# tamiya_camrobo_face_dotstar.net
KiCad netlist of a schematic drawn in EAGLE
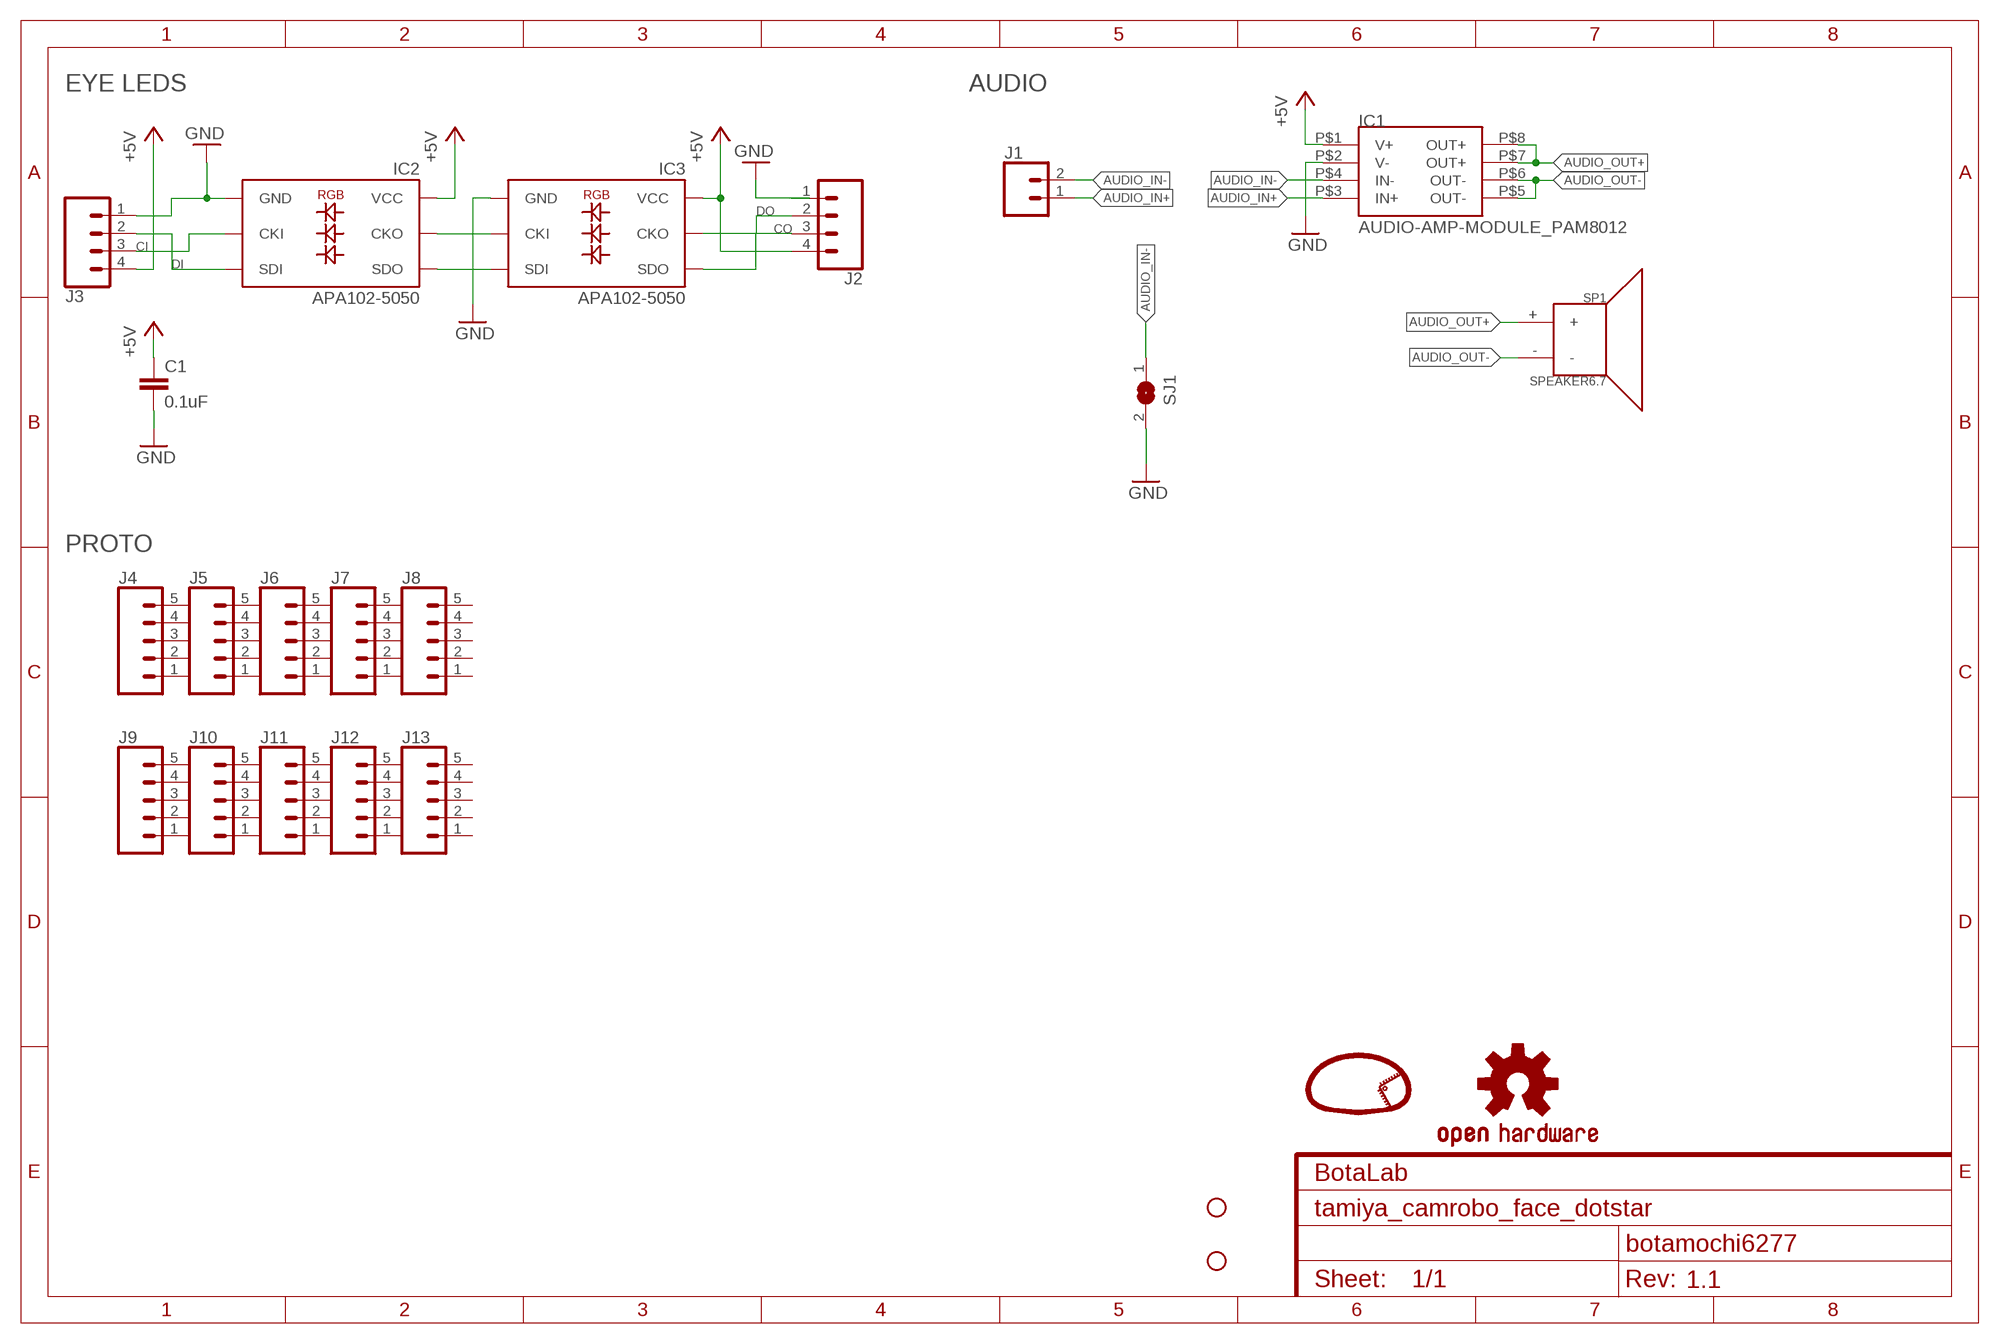
[diagram p0: schematic, sheet 1]

(export (version "E")
  (design (tool "Eeschema 10.0.6"))
  (components
    (comp (ref "C1")
      (value "0.1uF")
      (footprint "eagle-import:C1608")
      (libsource (lib "eagle-import") (part "C-EUC1608"))
    )
    (comp (ref "H1")
      (value "STAND-OFF")
      (footprint "eagle-import:STAND-OFF")
      (libsource (lib "eagle-import") (part "STAND-OFF"))
    )
    (comp (ref "H2")
      (value "STAND-OFF")
      (footprint "eagle-import:STAND-OFF")
      (libsource (lib "eagle-import") (part "STAND-OFF"))
    )
    (comp (ref "IC1")
      (value "AUDIO-AMP-MODULE_PAM8012")
      (footprint "eagle-import:AE-PAM8012")
      (libsource (lib "eagle-import") (part "AUDIO-AMP-MODULE_PAM8012"))
    )
    (comp (ref "IC2")
      (value "APA102-5050")
      (footprint "eagle-import:APA102C-5050")
      (libsource (lib "eagle-import") (part "APA102-5050"))
    )
    (comp (ref "IC3")
      (value "APA102-5050")
      (footprint "eagle-import:APA102C-5050")
      (libsource (lib "eagle-import") (part "APA102-5050"))
    )
    (comp (ref "J1")
      (value "CONN_02")
      (footprint "eagle-import:1X02")
      (libsource (lib "eagle-import") (part "CONN_02"))
    )
    (comp (ref "J2")
      (value "CONN_04")
      (footprint "eagle-import:1X04")
      (libsource (lib "eagle-import") (part "CONN_04"))
    )
    (comp (ref "J3")
      (value "CONN_04")
      (footprint "eagle-import:1X04")
      (libsource (lib "eagle-import") (part "CONN_04"))
    )
    (comp (ref "J4")
      (value "CONN_05NO_SILK")
      (footprint "eagle-import:1X05_NO_SILK")
      (libsource (lib "eagle-import") (part "CONN_05NO_SILK"))
    )
    (comp (ref "J5")
      (value "CONN_05NO_SILK")
      (footprint "eagle-import:1X05_NO_SILK")
      (libsource (lib "eagle-import") (part "CONN_05NO_SILK"))
    )
    (comp (ref "J6")
      (value "CONN_05NO_SILK")
      (footprint "eagle-import:1X05_NO_SILK")
      (libsource (lib "eagle-import") (part "CONN_05NO_SILK"))
    )
    (comp (ref "J7")
      (value "CONN_05NO_SILK")
      (footprint "eagle-import:1X05_NO_SILK")
      (libsource (lib "eagle-import") (part "CONN_05NO_SILK"))
    )
    (comp (ref "J8")
      (value "CONN_05NO_SILK")
      (footprint "eagle-import:1X05_NO_SILK")
      (libsource (lib "eagle-import") (part "CONN_05NO_SILK"))
    )
    (comp (ref "J9")
      (value "CONN_05NO_SILK")
      (footprint "eagle-import:1X05_NO_SILK")
      (libsource (lib "eagle-import") (part "CONN_05NO_SILK"))
    )
    (comp (ref "J10")
      (value "CONN_05NO_SILK")
      (footprint "eagle-import:1X05_NO_SILK")
      (libsource (lib "eagle-import") (part "CONN_05NO_SILK"))
    )
    (comp (ref "J11")
      (value "CONN_05NO_SILK")
      (footprint "eagle-import:1X05_NO_SILK")
      (libsource (lib "eagle-import") (part "CONN_05NO_SILK"))
    )
    (comp (ref "J12")
      (value "CONN_05NO_SILK")
      (footprint "eagle-import:1X05_NO_SILK")
      (libsource (lib "eagle-import") (part "CONN_05NO_SILK"))
    )
    (comp (ref "J13")
      (value "CONN_05NO_SILK")
      (footprint "eagle-import:1X05_NO_SILK")
      (libsource (lib "eagle-import") (part "CONN_05NO_SILK"))
    )
    (comp (ref "LOGO1")
      (value "LOGO")
      (footprint "eagle-import:LOGO")
      (libsource (lib "eagle-import") (part "LOGO"))
    )
    (comp (ref "LOGO2")
      (value "OSHW-LOGOS")
      (footprint "eagle-import:OSHW-LOGO-S")
      (libsource (lib "eagle-import") (part "OSHW-LOGOS"))
    )
    (comp (ref "SJ1") (value "SJ") (footprint "eagle-import:SJ") (libsource (lib "eagle-import") (part "SJ")))
    (comp (ref "SP1")
      (value "SPEAKER6.7")
      (footprint "eagle-import:SPEAKER-6.7MM")
      (libsource (lib "eagle-import") (part "SPEAKER6.7"))
    )
  )
  (nets
    (net (code "1") (name "+5V") (class "Default")
      (node (ref "C1") (pin "1") (pinfunction "1_1") (pintype "passive"))
      (node (ref "IC1") (pin "P$1") (pinfunction "V+_P$1") (pintype "power_in"))
      (node (ref "IC2") (pin "VCC") (pinfunction "VCC_VCC") (pintype "power_in"))
      (node (ref "IC3") (pin "VCC") (pinfunction "VCC_VCC") (pintype "power_in"))
      (node (ref "J2") (pin "4") (pinfunction "4_4") (pintype "passive"))
      (node (ref "J3") (pin "4") (pinfunction "4_4") (pintype "passive"))
    )
    (net (code "2") (name "/CI") (class "Default")
      (node (ref "IC2") (pin "CKI") (pinfunction "CKI_CKI") (pintype "input"))
      (node (ref "J3") (pin "3") (pinfunction "3_3") (pintype "passive"))
    )
    (net (code "3") (name "/CO") (class "Default")
      (node (ref "IC3") (pin "CKO") (pinfunction "CKO_CKO") (pintype "output"))
      (node (ref "J2") (pin "3") (pinfunction "3_3") (pintype "passive"))
    )
    (net (code "4") (name "/DI") (class "Default")
      (node (ref "IC2") (pin "SDI") (pinfunction "SDI_SDI") (pintype "input"))
      (node (ref "J3") (pin "2") (pinfunction "2_2") (pintype "passive"))
    )
    (net (code "5") (name "/DO") (class "Default")
      (node (ref "IC3") (pin "SDO") (pinfunction "SDO_SDO") (pintype "output"))
      (node (ref "J2") (pin "2") (pinfunction "2_2") (pintype "passive"))
    )
    (net (code "6") (name "AUDIO_IN+") (class "Default")
      (node (ref "IC1") (pin "P$3") (pinfunction "IN+_P$3") (pintype "input"))
      (node (ref "J1") (pin "1") (pinfunction "1_1") (pintype "passive"))
    )
    (net (code "7") (name "AUDIO_IN-") (class "Default")
      (node (ref "IC1") (pin "P$4") (pinfunction "IN-_P$4") (pintype "input"))
      (node (ref "J1") (pin "2") (pinfunction "2_2") (pintype "passive"))
      (node (ref "SJ1") (pin "1") (pinfunction "1_1") (pintype "passive"))
    )
    (net (code "8") (name "AUDIO_OUT+") (class "Default")
      (node (ref "IC1") (pin "P$7") (pinfunction "OUT+_P$7") (pintype "output"))
      (node (ref "IC1") (pin "P$8") (pinfunction "OUT+_P$8") (pintype "output"))
      (node (ref "SP1") (pin "+") (pinfunction "+_+") (pintype "bidirectional"))
    )
    (net (code "9") (name "AUDIO_OUT-") (class "Default")
      (node (ref "IC1") (pin "P$5") (pinfunction "OUT-_P$5") (pintype "output"))
      (node (ref "IC1") (pin "P$6") (pinfunction "OUT-_P$6") (pintype "output"))
      (node (ref "SP1") (pin "-") (pinfunction "-_-") (pintype "bidirectional"))
    )
    (net (code "10") (name "GND") (class "Default")
      (node (ref "C1") (pin "2") (pinfunction "2_2") (pintype "passive"))
      (node (ref "IC1") (pin "P$2") (pinfunction "V-_P$2") (pintype "power_in"))
      (node (ref "IC2") (pin "GND") (pinfunction "GND_GND") (pintype "power_in"))
      (node (ref "IC3") (pin "GND") (pinfunction "GND_GND") (pintype "power_in"))
      (node (ref "J2") (pin "1") (pinfunction "1_1") (pintype "passive"))
      (node (ref "J3") (pin "1") (pinfunction "1_1") (pintype "passive"))
      (node (ref "SJ1") (pin "2") (pinfunction "2_2") (pintype "passive"))
    )
    (net (code "11") (name "Net-(IC2-PadCKO)") (class "Default")
      (node (ref "IC2") (pin "CKO") (pinfunction "CKO_CKO") (pintype "output"))
      (node (ref "IC3") (pin "CKI") (pinfunction "CKI_CKI") (pintype "input"))
    )
    (net (code "12") (name "Net-(IC2-PadSDO)") (class "Default")
      (node (ref "IC2") (pin "SDO") (pinfunction "SDO_SDO") (pintype "output"))
      (node (ref "IC3") (pin "SDI") (pinfunction "SDI_SDI") (pintype "input"))
    )
    (net (code "13") (name "unconnected-(J4-Pad1)") (class "Default")
      (node (ref "J4") (pin "1") (pinfunction "1_1") (pintype "passive"))
    )
    (net (code "14") (name "unconnected-(J4-Pad2)") (class "Default")
      (node (ref "J4") (pin "2") (pinfunction "2_2") (pintype "passive"))
    )
    (net (code "15") (name "unconnected-(J4-Pad3)") (class "Default")
      (node (ref "J4") (pin "3") (pinfunction "3_3") (pintype "passive"))
    )
    (net (code "16") (name "unconnected-(J4-Pad4)") (class "Default")
      (node (ref "J4") (pin "4") (pinfunction "4_4") (pintype "passive"))
    )
    (net (code "17") (name "unconnected-(J4-Pad5)") (class "Default")
      (node (ref "J4") (pin "5") (pinfunction "5_5") (pintype "passive"))
    )
    (net (code "18") (name "unconnected-(J5-Pad1)") (class "Default")
      (node (ref "J5") (pin "1") (pinfunction "1_1") (pintype "passive"))
    )
    (net (code "19") (name "unconnected-(J5-Pad2)") (class "Default")
      (node (ref "J5") (pin "2") (pinfunction "2_2") (pintype "passive"))
    )
    (net (code "20") (name "unconnected-(J5-Pad3)") (class "Default")
      (node (ref "J5") (pin "3") (pinfunction "3_3") (pintype "passive"))
    )
    (net (code "21") (name "unconnected-(J5-Pad4)") (class "Default")
      (node (ref "J5") (pin "4") (pinfunction "4_4") (pintype "passive"))
    )
    (net (code "22") (name "unconnected-(J5-Pad5)") (class "Default")
      (node (ref "J5") (pin "5") (pinfunction "5_5") (pintype "passive"))
    )
    (net (code "23") (name "unconnected-(J6-Pad1)") (class "Default")
      (node (ref "J6") (pin "1") (pinfunction "1_1") (pintype "passive"))
    )
    (net (code "24") (name "unconnected-(J6-Pad2)") (class "Default")
      (node (ref "J6") (pin "2") (pinfunction "2_2") (pintype "passive"))
    )
    (net (code "25") (name "unconnected-(J6-Pad3)") (class "Default")
      (node (ref "J6") (pin "3") (pinfunction "3_3") (pintype "passive"))
    )
    (net (code "26") (name "unconnected-(J6-Pad4)") (class "Default")
      (node (ref "J6") (pin "4") (pinfunction "4_4") (pintype "passive"))
    )
    (net (code "27") (name "unconnected-(J6-Pad5)") (class "Default")
      (node (ref "J6") (pin "5") (pinfunction "5_5") (pintype "passive"))
    )
    (net (code "28") (name "unconnected-(J7-Pad1)") (class "Default")
      (node (ref "J7") (pin "1") (pinfunction "1_1") (pintype "passive"))
    )
    (net (code "29") (name "unconnected-(J7-Pad2)") (class "Default")
      (node (ref "J7") (pin "2") (pinfunction "2_2") (pintype "passive"))
    )
    (net (code "30") (name "unconnected-(J7-Pad3)") (class "Default")
      (node (ref "J7") (pin "3") (pinfunction "3_3") (pintype "passive"))
    )
    (net (code "31") (name "unconnected-(J7-Pad4)") (class "Default")
      (node (ref "J7") (pin "4") (pinfunction "4_4") (pintype "passive"))
    )
    (net (code "32") (name "unconnected-(J7-Pad5)") (class "Default")
      (node (ref "J7") (pin "5") (pinfunction "5_5") (pintype "passive"))
    )
    (net (code "33") (name "unconnected-(J8-Pad1)") (class "Default")
      (node (ref "J8") (pin "1") (pinfunction "1_1") (pintype "passive"))
    )
    (net (code "34") (name "unconnected-(J8-Pad2)") (class "Default")
      (node (ref "J8") (pin "2") (pinfunction "2_2") (pintype "passive"))
    )
    (net (code "35") (name "unconnected-(J8-Pad3)") (class "Default")
      (node (ref "J8") (pin "3") (pinfunction "3_3") (pintype "passive"))
    )
    (net (code "36") (name "unconnected-(J8-Pad4)") (class "Default")
      (node (ref "J8") (pin "4") (pinfunction "4_4") (pintype "passive"))
    )
    (net (code "37") (name "unconnected-(J8-Pad5)") (class "Default")
      (node (ref "J8") (pin "5") (pinfunction "5_5") (pintype "passive"))
    )
    (net (code "38") (name "unconnected-(J9-Pad1)") (class "Default")
      (node (ref "J9") (pin "1") (pinfunction "1_1") (pintype "passive"))
    )
    (net (code "39") (name "unconnected-(J9-Pad2)") (class "Default")
      (node (ref "J9") (pin "2") (pinfunction "2_2") (pintype "passive"))
    )
    (net (code "40") (name "unconnected-(J9-Pad3)") (class "Default")
      (node (ref "J9") (pin "3") (pinfunction "3_3") (pintype "passive"))
    )
    (net (code "41") (name "unconnected-(J9-Pad4)") (class "Default")
      (node (ref "J9") (pin "4") (pinfunction "4_4") (pintype "passive"))
    )
    (net (code "42") (name "unconnected-(J9-Pad5)") (class "Default")
      (node (ref "J9") (pin "5") (pinfunction "5_5") (pintype "passive"))
    )
    (net (code "43") (name "unconnected-(J10-Pad1)") (class "Default")
      (node (ref "J10") (pin "1") (pinfunction "1_1") (pintype "passive"))
    )
    (net (code "44") (name "unconnected-(J10-Pad2)") (class "Default")
      (node (ref "J10") (pin "2") (pinfunction "2_2") (pintype "passive"))
    )
    (net (code "45") (name "unconnected-(J10-Pad3)") (class "Default")
      (node (ref "J10") (pin "3") (pinfunction "3_3") (pintype "passive"))
    )
    (net (code "46") (name "unconnected-(J10-Pad4)") (class "Default")
      (node (ref "J10") (pin "4") (pinfunction "4_4") (pintype "passive"))
    )
    (net (code "47") (name "unconnected-(J10-Pad5)") (class "Default")
      (node (ref "J10") (pin "5") (pinfunction "5_5") (pintype "passive"))
    )
    (net (code "48") (name "unconnected-(J11-Pad1)") (class "Default")
      (node (ref "J11") (pin "1") (pinfunction "1_1") (pintype "passive"))
    )
    (net (code "49") (name "unconnected-(J11-Pad2)") (class "Default")
      (node (ref "J11") (pin "2") (pinfunction "2_2") (pintype "passive"))
    )
    (net (code "50") (name "unconnected-(J11-Pad3)") (class "Default")
      (node (ref "J11") (pin "3") (pinfunction "3_3") (pintype "passive"))
    )
    (net (code "51") (name "unconnected-(J11-Pad4)") (class "Default")
      (node (ref "J11") (pin "4") (pinfunction "4_4") (pintype "passive"))
    )
    (net (code "52") (name "unconnected-(J11-Pad5)") (class "Default")
      (node (ref "J11") (pin "5") (pinfunction "5_5") (pintype "passive"))
    )
    (net (code "53") (name "unconnected-(J12-Pad1)") (class "Default")
      (node (ref "J12") (pin "1") (pinfunction "1_1") (pintype "passive"))
    )
    (net (code "54") (name "unconnected-(J12-Pad2)") (class "Default")
      (node (ref "J12") (pin "2") (pinfunction "2_2") (pintype "passive"))
    )
    (net (code "55") (name "unconnected-(J12-Pad3)") (class "Default")
      (node (ref "J12") (pin "3") (pinfunction "3_3") (pintype "passive"))
    )
    (net (code "56") (name "unconnected-(J12-Pad4)") (class "Default")
      (node (ref "J12") (pin "4") (pinfunction "4_4") (pintype "passive"))
    )
    (net (code "57") (name "unconnected-(J12-Pad5)") (class "Default")
      (node (ref "J12") (pin "5") (pinfunction "5_5") (pintype "passive"))
    )
    (net (code "58") (name "unconnected-(J13-Pad1)") (class "Default")
      (node (ref "J13") (pin "1") (pinfunction "1_1") (pintype "passive"))
    )
    (net (code "59") (name "unconnected-(J13-Pad2)") (class "Default")
      (node (ref "J13") (pin "2") (pinfunction "2_2") (pintype "passive"))
    )
    (net (code "60") (name "unconnected-(J13-Pad3)") (class "Default")
      (node (ref "J13") (pin "3") (pinfunction "3_3") (pintype "passive"))
    )
    (net (code "61") (name "unconnected-(J13-Pad4)") (class "Default")
      (node (ref "J13") (pin "4") (pinfunction "4_4") (pintype "passive"))
    )
    (net (code "62") (name "unconnected-(J13-Pad5)") (class "Default")
      (node (ref "J13") (pin "5") (pinfunction "5_5") (pintype "passive"))
    )
  )
)
